# bvsys1.net
KiCad netlist of a schematic drawn in EAGLE
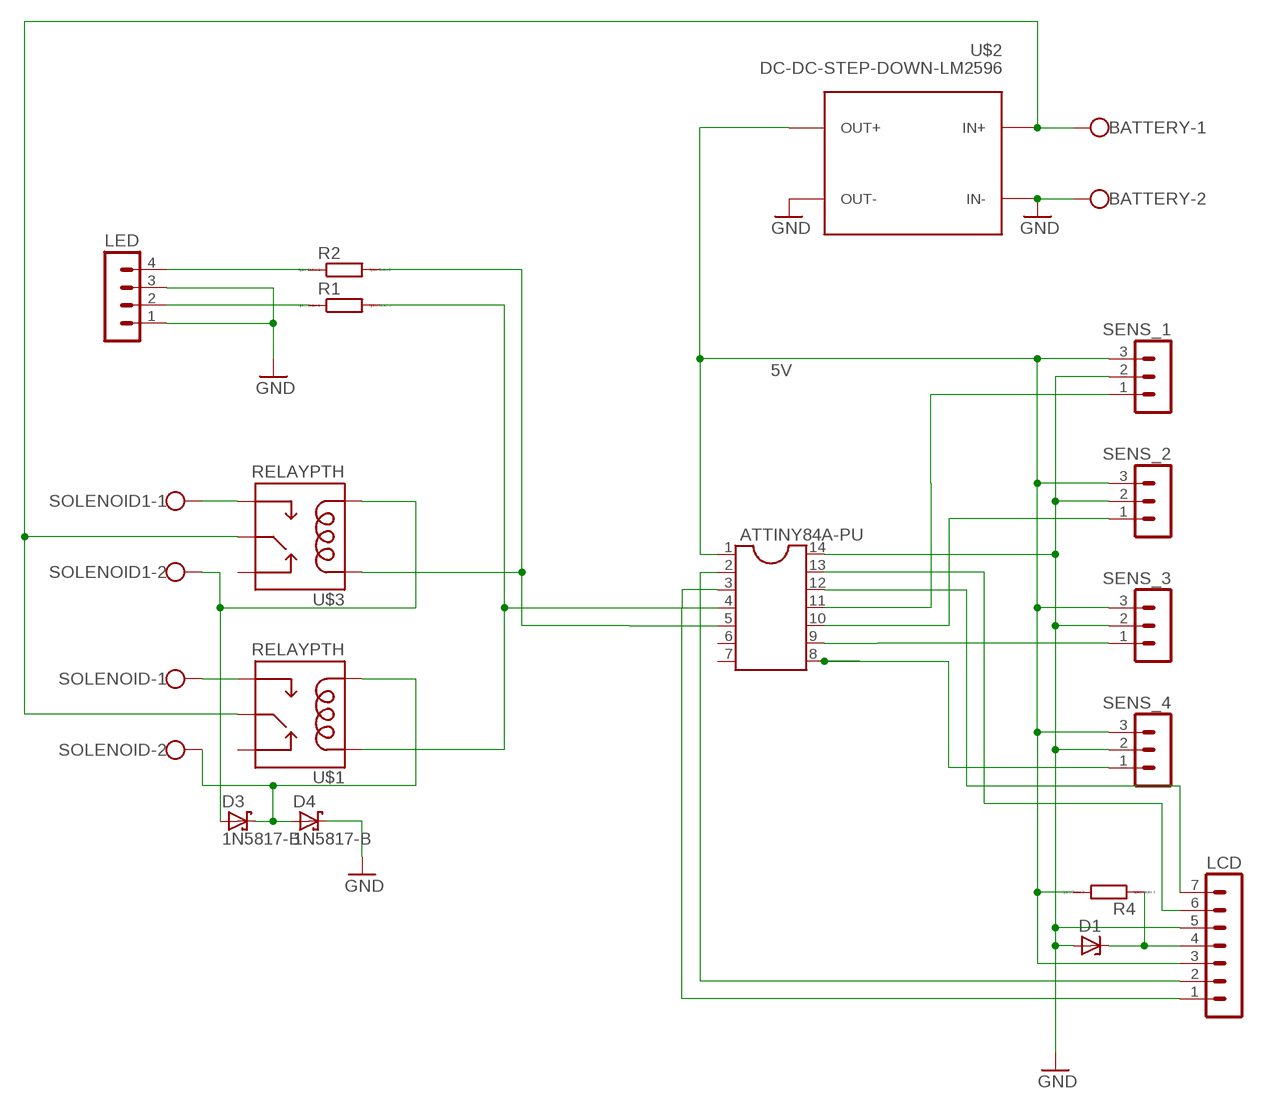
[diagram p0: schematic, sheet 1]

(export (version "E")
  (design (tool "Eeschema 10.0.6"))
  (components
    (comp (ref "ATTINY84A-PU")
      (value "DIL14S")
      (footprint "eagle-import:SOCKET-14")
      (libsource (lib "eagle-import") (part "DIL14S"))
    )
    (comp (ref "BATTERY")
      (value "W237-102")
      (footprint "eagle-import:W237-102")
      (fields (field (name "MPN") "237-102"))
      (libsource (lib "eagle-import") (part "W237-102"))
    )
    (comp (ref "D1")
      (value "ZENER-DIODEDO34-7")
      (footprint "eagle-import:DO34Z7")
      (libsource (lib "eagle-import") (part "ZENER-DIODEDO34-7"))
    )
    (comp (ref "D3")
      (value "1N5817-B")
      (footprint "eagle-import:DO41-7.6")
      (libsource (lib "eagle-import") (part "1N5817-B"))
    )
    (comp (ref "D4")
      (value "1N5817-B")
      (footprint "eagle-import:DO41-7.6")
      (libsource (lib "eagle-import") (part "1N5817-B"))
    )
    (comp (ref "LCD")
      (value "MA07-1")
      (footprint "eagle-import:MA07-1")
      (libsource (lib "eagle-import") (part "MA07-1"))
    )
    (comp (ref "LED")
      (value "MA04-1")
      (footprint "eagle-import:MA04-1")
      (libsource (lib "eagle-import") (part "MA04-1"))
    )
    (comp (ref "R1")
      (value "R0204/7")
      (footprint "eagle-import:0204_7")
      (libsource (lib "eagle-import") (part "R0204/7"))
    )
    (comp (ref "R2")
      (value "R0204/7")
      (footprint "eagle-import:0204_7")
      (libsource (lib "eagle-import") (part "R0204/7"))
    )
    (comp (ref "R4")
      (value "R0204/7")
      (footprint "eagle-import:0204_7")
      (libsource (lib "eagle-import") (part "R0204/7"))
    )
    (comp (ref "SENS_1")
      (value "MA03-1")
      (footprint "eagle-import:MA03-1")
      (libsource (lib "eagle-import") (part "MA03-1"))
    )
    (comp (ref "SENS_2")
      (value "MA03-1")
      (footprint "eagle-import:MA03-1")
      (libsource (lib "eagle-import") (part "MA03-1"))
    )
    (comp (ref "SENS_3")
      (value "MA03-1")
      (footprint "eagle-import:MA03-1")
      (libsource (lib "eagle-import") (part "MA03-1"))
    )
    (comp (ref "SENS_4")
      (value "MA03-1")
      (footprint "eagle-import:MA03-1")
      (libsource (lib "eagle-import") (part "MA03-1"))
    )
    (comp (ref "SOLENOID")
      (value "W237-102")
      (footprint "eagle-import:W237-102")
      (fields (field (name "MPN") "237-102"))
      (libsource (lib "eagle-import") (part "W237-102"))
    )
    (comp (ref "SOLENOID1")
      (value "W237-102")
      (footprint "eagle-import:W237-102")
      (fields (field (name "MPN") "237-102"))
      (libsource (lib "eagle-import") (part "W237-102"))
    )
    (comp (ref "U$1")
      (value "RELAYPTH")
      (footprint "eagle-import:SRD-05VDC-SL-C")
      (libsource (lib "eagle-import") (part "RELAYPTH"))
    )
    (comp (ref "U$2")
      (value "DC-DC-STEP-DOWN-LM2596")
      (footprint "eagle-import:DC-DC-STEP-DOWN-LM2596")
      (libsource (lib "eagle-import") (part "DC-DC-STEP-DOWN-LM2596"))
    )
    (comp (ref "U$3")
      (value "RELAYPTH")
      (footprint "eagle-import:SRD-05VDC-SL-C")
      (libsource (lib "eagle-import") (part "RELAYPTH"))
    )
  )
  (nets
    (net (code "1") (name "/5V") (class "Default")
      (node (ref "ATTINY84A-PU") (pin "1") (pinfunction "1_1") (pintype "passive"))
      (node (ref "LCD") (pin "3") (pinfunction "3_3") (pintype "passive"))
      (node (ref "R4") (pin "2") (pinfunction "2_2") (pintype "passive"))
      (node (ref "SENS_1") (pin "3") (pinfunction "3_3") (pintype "passive"))
      (node (ref "SENS_2") (pin "3") (pinfunction "3_3") (pintype "passive"))
      (node (ref "SENS_3") (pin "3") (pinfunction "3_3") (pintype "passive"))
      (node (ref "SENS_4") (pin "3") (pinfunction "3_3") (pintype "passive"))
      (node (ref "U$2") (pin "OUT+") (pinfunction "OUT+_OUT+") (pintype "bidirectional"))
    )
    (net (code "2") (name "GND") (class "Default")
      (node (ref "ATTINY84A-PU") (pin "14") (pinfunction "14_14") (pintype "passive"))
      (node (ref "BATTERY") (pin "2") (pinfunction "KL_2") (pintype "passive"))
      (node (ref "D1") (pin "A") (pinfunction "A_A") (pintype "passive"))
      (node (ref "D4") (pin "C") (pinfunction "C_C") (pintype "passive"))
      (node (ref "LCD") (pin "5") (pinfunction "5_5") (pintype "passive"))
      (node (ref "LED") (pin "1") (pinfunction "1_1") (pintype "passive"))
      (node (ref "LED") (pin "3") (pinfunction "3_3") (pintype "passive"))
      (node (ref "SENS_1") (pin "2") (pinfunction "2_2") (pintype "passive"))
      (node (ref "SENS_2") (pin "2") (pinfunction "2_2") (pintype "passive"))
      (node (ref "SENS_3") (pin "2") (pinfunction "2_2") (pintype "passive"))
      (node (ref "SENS_4") (pin "2") (pinfunction "2_2") (pintype "passive"))
      (node (ref "U$2") (pin "IN-") (pinfunction "IN-_IN-") (pintype "bidirectional"))
      (node (ref "U$2") (pin "OUT-") (pinfunction "OUT-_OUT-") (pintype "bidirectional"))
    )
    (net (code "3") (name "Net-(ATTINY84A-PU-Pad2)") (class "Default")
      (node (ref "ATTINY84A-PU") (pin "2") (pinfunction "2_2") (pintype "passive"))
      (node (ref "LCD") (pin "2") (pinfunction "2_2") (pintype "passive"))
    )
    (net (code "4") (name "Net-(ATTINY84A-PU-Pad3)") (class "Default")
      (node (ref "ATTINY84A-PU") (pin "3") (pinfunction "3_3") (pintype "passive"))
      (node (ref "LCD") (pin "1") (pinfunction "1_1") (pintype "passive"))
    )
    (net (code "5") (name "Net-(ATTINY84A-PU-Pad4)") (class "Default")
      (node (ref "ATTINY84A-PU") (pin "4") (pinfunction "4_4") (pintype "passive"))
      (node (ref "R1") (pin "2") (pinfunction "2_2") (pintype "passive"))
      (node (ref "U$1") (pin "COIL1") (pinfunction "COIL1_COIL1") (pintype "bidirectional"))
    )
    (net (code "6") (name "Net-(ATTINY84A-PU-Pad5)") (class "Default")
      (node (ref "ATTINY84A-PU") (pin "5") (pinfunction "5_5") (pintype "passive"))
      (node (ref "R2") (pin "2") (pinfunction "2_2") (pintype "passive"))
      (node (ref "U$3") (pin "COIL1") (pinfunction "COIL1_COIL1") (pintype "bidirectional"))
    )
    (net (code "7") (name "Net-(ATTINY84A-PU-Pad8)") (class "Default")
      (node (ref "ATTINY84A-PU") (pin "8") (pinfunction "8_8") (pintype "passive"))
      (node (ref "SENS_4") (pin "1") (pinfunction "1_1") (pintype "passive"))
    )
    (net (code "8") (name "Net-(ATTINY84A-PU-Pad9)") (class "Default")
      (node (ref "ATTINY84A-PU") (pin "9") (pinfunction "9_9") (pintype "passive"))
      (node (ref "SENS_3") (pin "1") (pinfunction "1_1") (pintype "passive"))
    )
    (net (code "9") (name "Net-(ATTINY84A-PU-Pad10)") (class "Default")
      (node (ref "ATTINY84A-PU") (pin "10") (pinfunction "10_10") (pintype "passive"))
      (node (ref "SENS_2") (pin "1") (pinfunction "1_1") (pintype "passive"))
    )
    (net (code "10") (name "Net-(ATTINY84A-PU-Pad11)") (class "Default")
      (node (ref "ATTINY84A-PU") (pin "11") (pinfunction "11_11") (pintype "passive"))
      (node (ref "SENS_1") (pin "1") (pinfunction "1_1") (pintype "passive"))
    )
    (net (code "11") (name "Net-(ATTINY84A-PU-Pad12)") (class "Default")
      (node (ref "ATTINY84A-PU") (pin "12") (pinfunction "12_12") (pintype "passive"))
      (node (ref "LCD") (pin "7") (pinfunction "7_7") (pintype "passive"))
    )
    (net (code "12") (name "Net-(ATTINY84A-PU-Pad13)") (class "Default")
      (node (ref "ATTINY84A-PU") (pin "13") (pinfunction "13_13") (pintype "passive"))
      (node (ref "LCD") (pin "6") (pinfunction "6_6") (pintype "passive"))
    )
    (net (code "13") (name "Net-(BATTERYA-KL)") (class "Default")
      (node (ref "BATTERY") (pin "1") (pinfunction "KL_1") (pintype "passive"))
      (node (ref "U$1") (pin "SWCOMMON") (pinfunction "SWCOMMON_SWCOMMON") (pintype "bidirectional"))
      (node (ref "U$2") (pin "IN+") (pinfunction "IN+_IN+") (pintype "bidirectional"))
      (node (ref "U$3") (pin "SWCOMMON") (pinfunction "SWCOMMON_SWCOMMON") (pintype "bidirectional"))
    )
    (net (code "14") (name "Net-(D1-PadC)") (class "Default")
      (node (ref "D1") (pin "C") (pinfunction "C_C") (pintype "passive"))
      (node (ref "LCD") (pin "4") (pinfunction "4_4") (pintype "passive"))
      (node (ref "R4") (pin "1") (pinfunction "1_1") (pintype "passive"))
    )
    (net (code "15") (name "Net-(LED-Pad2)") (class "Default")
      (node (ref "LED") (pin "2") (pinfunction "2_2") (pintype "passive"))
      (node (ref "R1") (pin "1") (pinfunction "1_1") (pintype "passive"))
    )
    (net (code "16") (name "Net-(LED-Pad4)") (class "Default")
      (node (ref "LED") (pin "4") (pinfunction "4_4") (pintype "passive"))
      (node (ref "R2") (pin "1") (pinfunction "1_1") (pintype "passive"))
    )
    (net (code "17") (name "Net-(SOLENOID1A-KL)") (class "Default")
      (node (ref "SOLENOID1") (pin "1") (pinfunction "KL_1") (pintype "passive"))
      (node (ref "U$3") (pin "SWOPEN") (pinfunction "SWOPEN_SWOPEN") (pintype "bidirectional"))
    )
    (net (code "18") (name "Net-(SOLENOID1B-KL)") (class "Default")
      (node (ref "D3") (pin "A") (pinfunction "A_A") (pintype "passive"))
      (node (ref "SOLENOID1") (pin "2") (pinfunction "KL_2") (pintype "passive"))
      (node (ref "U$3") (pin "COIL0") (pinfunction "COIL0_COIL0") (pintype "bidirectional"))
    )
    (net (code "19") (name "Net-(SOLENOIDA-KL)") (class "Default")
      (node (ref "SOLENOID") (pin "1") (pinfunction "KL_1") (pintype "passive"))
      (node (ref "U$1") (pin "SWOPEN") (pinfunction "SWOPEN_SWOPEN") (pintype "bidirectional"))
    )
    (net (code "20") (name "Net-(SOLENOIDB-KL)") (class "Default")
      (node (ref "D3") (pin "C") (pinfunction "C_C") (pintype "passive"))
      (node (ref "D4") (pin "A") (pinfunction "A_A") (pintype "passive"))
      (node (ref "SOLENOID") (pin "2") (pinfunction "KL_2") (pintype "passive"))
      (node (ref "U$1") (pin "COIL0") (pinfunction "COIL0_COIL0") (pintype "bidirectional"))
    )
    (net (code "21") (name "unconnected-(ATTINY84A-PU-Pad6)") (class "Default")
      (node (ref "ATTINY84A-PU") (pin "6") (pinfunction "6_6") (pintype "passive"))
    )
    (net (code "22") (name "unconnected-(ATTINY84A-PU-Pad7)") (class "Default")
      (node (ref "ATTINY84A-PU") (pin "7") (pinfunction "7_7") (pintype "passive"))
    )
    (net (code "23") (name "unconnected-(U$1-SWCLOSE-PadSWCLOSED)") (class "Default")
      (node (ref "U$1") (pin "SWCLOSED") (pinfunction "SWCLOSE_SWCLOSED") (pintype "bidirectional"))
    )
    (net (code "24") (name "unconnected-(U$3-SWCLOSE-PadSWCLOSED)") (class "Default")
      (node (ref "U$3") (pin "SWCLOSED") (pinfunction "SWCLOSE_SWCLOSED") (pintype "bidirectional"))
    )
  )
)
